# marshall.net
KiCad netlist of a schematic drawn in EAGLE
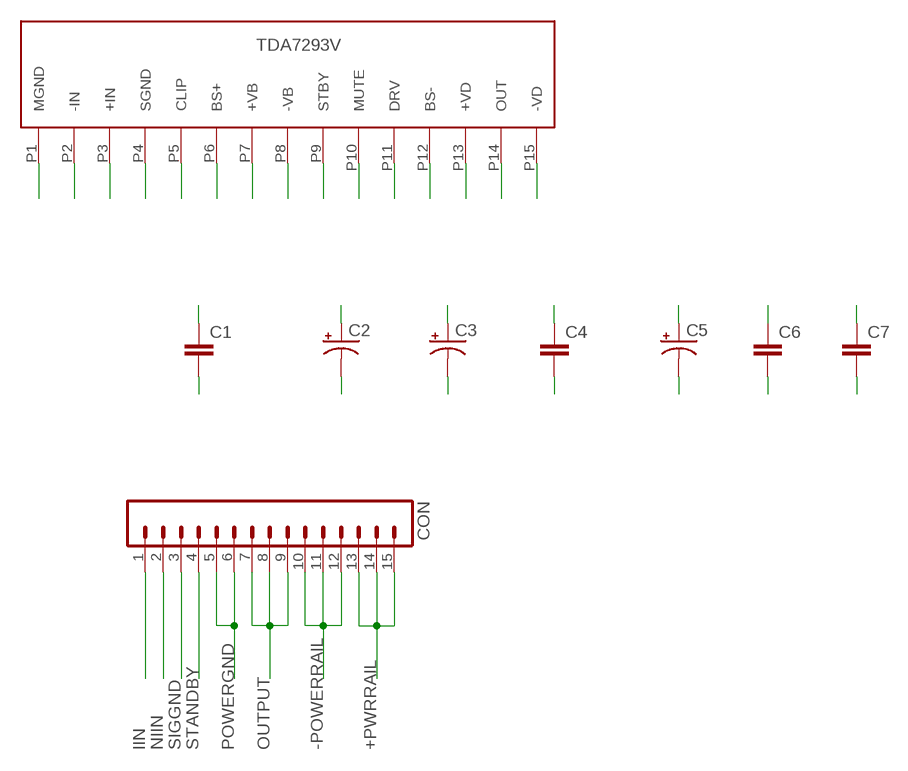
[diagram p0: schematic, sheet 1]

(export (version "E")
  (design (tool "Eeschema 10.0.6"))
  (components
    (comp (ref "C1")
      (value "CAPPTH1")
      (footprint "eagle-import:CAP-PTH-5MM")
      (libsource (lib "eagle-import") (part "CAPPTH1"))
    )
    (comp (ref "C2")
      (value "CAP_POLPTH2")
      (footprint "eagle-import:CPOL-RADIAL-10UF-25V")
      (libsource (lib "eagle-import") (part "CAP_POLPTH2"))
    )
    (comp (ref "C3")
      (value "CAP_POLPTH2")
      (footprint "eagle-import:CPOL-RADIAL-10UF-25V")
      (libsource (lib "eagle-import") (part "CAP_POLPTH2"))
    )
    (comp (ref "C4")
      (value "CAPPTH1")
      (footprint "eagle-import:CAP-PTH-5MM")
      (libsource (lib "eagle-import") (part "CAPPTH1"))
    )
    (comp (ref "C5")
      (value "CAP_POLPTH2")
      (footprint "eagle-import:CPOL-RADIAL-10UF-25V")
      (libsource (lib "eagle-import") (part "CAP_POLPTH2"))
    )
    (comp (ref "C6")
      (value "CAPPTH1")
      (footprint "eagle-import:CAP-PTH-5MM")
      (libsource (lib "eagle-import") (part "CAPPTH1"))
    )
    (comp (ref "C7")
      (value "CAPPTH1")
      (footprint "eagle-import:CAP-PTH-5MM")
      (libsource (lib "eagle-import") (part "CAPPTH1"))
    )
    (comp (ref "CON")
      (value "M15")
      (footprint "eagle-import:1X15")
      (libsource (lib "eagle-import") (part "M15"))
    )
    (comp (ref "U$1")
      (value "TDA7293V")
      (footprint "eagle-import:TDA7293V")
      (libsource (lib "eagle-import") (part "TDA7293V"))
    )
  )
  (nets
    (net (code "1") (name "/+PWRRAIL") (class "Default")
      (node (ref "C1") (pin "1") (pinfunction "1_1") (pintype "passive"))
      (node (ref "C2") (pin "1") (pinfunction "+_1") (pintype "passive"))
      (node (ref "CON") (pin "13") (pinfunction "13_13") (pintype "passive"))
      (node (ref "CON") (pin "14") (pinfunction "14_14") (pintype "passive"))
      (node (ref "CON") (pin "15") (pinfunction "15_15") (pintype "passive"))
      (node (ref "U$1") (pin "P10") (pinfunction "MUTE_P10") (pintype "bidirectional"))
      (node (ref "U$1") (pin "P13") (pinfunction "+VD_P13") (pintype "bidirectional"))
      (node (ref "U$1") (pin "P7") (pinfunction "+VB_P7") (pintype "bidirectional"))
    )
    (net (code "2") (name "/-POWERRAIL") (class "Default")
      (node (ref "C3") (pin "2") (pinfunction "-_2") (pintype "passive"))
      (node (ref "C4") (pin "1") (pinfunction "1_1") (pintype "passive"))
      (node (ref "CON") (pin "10") (pinfunction "10_10") (pintype "passive"))
      (node (ref "CON") (pin "11") (pinfunction "11_11") (pintype "passive"))
      (node (ref "CON") (pin "12") (pinfunction "12_12") (pintype "passive"))
      (node (ref "U$1") (pin "P15") (pinfunction "-VD_P15") (pintype "bidirectional"))
      (node (ref "U$1") (pin "P8") (pinfunction "-VB_P8") (pintype "bidirectional"))
    )
    (net (code "3") (name "/C5+") (class "Default")
      (node (ref "C5") (pin "1") (pinfunction "+_1") (pintype "passive"))
      (node (ref "U$1") (pin "P12") (pinfunction "BS-_P12") (pintype "bidirectional"))
    )
    (net (code "4") (name "/C5-") (class "Default")
      (node (ref "C5") (pin "2") (pinfunction "-_2") (pintype "passive"))
      (node (ref "U$1") (pin "P6") (pinfunction "BS+_P6") (pintype "bidirectional"))
    )
    (net (code "5") (name "/IIN") (class "Default")
      (node (ref "C6") (pin "2") (pinfunction "2_2") (pintype "passive"))
      (node (ref "C7") (pin "2") (pinfunction "2_2") (pintype "passive"))
      (node (ref "CON") (pin "1") (pinfunction "1_1") (pintype "passive"))
    )
    (net (code "6") (name "/NIIN") (class "Default")
      (node (ref "C6") (pin "1") (pinfunction "1_1") (pintype "passive"))
      (node (ref "CON") (pin "2") (pinfunction "2_2") (pintype "passive"))
      (node (ref "U$1") (pin "P3") (pinfunction "+IN_P3") (pintype "bidirectional"))
    )
    (net (code "7") (name "/OUTPUT") (class "Default")
      (node (ref "CON") (pin "7") (pinfunction "7_7") (pintype "passive"))
      (node (ref "CON") (pin "8") (pinfunction "8_8") (pintype "passive"))
      (node (ref "CON") (pin "9") (pinfunction "9_9") (pintype "passive"))
      (node (ref "U$1") (pin "P14") (pinfunction "OUT_P14") (pintype "bidirectional"))
    )
    (net (code "8") (name "/POWERGND") (class "Default")
      (node (ref "C1") (pin "2") (pinfunction "2_2") (pintype "passive"))
      (node (ref "C2") (pin "2") (pinfunction "-_2") (pintype "passive"))
      (node (ref "C3") (pin "1") (pinfunction "+_1") (pintype "passive"))
      (node (ref "C4") (pin "2") (pinfunction "2_2") (pintype "passive"))
      (node (ref "CON") (pin "5") (pinfunction "5_5") (pintype "passive"))
      (node (ref "CON") (pin "6") (pinfunction "6_6") (pintype "passive"))
      (node (ref "U$1") (pin "P1") (pinfunction "MGND_P1") (pintype "bidirectional"))
    )
    (net (code "9") (name "/SIGGND") (class "Default")
      (node (ref "C7") (pin "1") (pinfunction "1_1") (pintype "passive"))
      (node (ref "CON") (pin "3") (pinfunction "3_3") (pintype "passive"))
      (node (ref "U$1") (pin "P4") (pinfunction "SGND_P4") (pintype "bidirectional"))
    )
    (net (code "10") (name "/STANDBY") (class "Default")
      (node (ref "CON") (pin "4") (pinfunction "4_4") (pintype "passive"))
      (node (ref "U$1") (pin "P9") (pinfunction "STBY_P9") (pintype "bidirectional"))
    )
    (net (code "11") (name "unconnected-(U$1--IN-PadP2)") (class "Default")
      (node (ref "U$1") (pin "P2") (pinfunction "-IN_P2") (pintype "bidirectional"))
    )
    (net (code "12") (name "unconnected-(U$1-CLIP-PadP5)") (class "Default")
      (node (ref "U$1") (pin "P5") (pinfunction "CLIP_P5") (pintype "bidirectional"))
    )
    (net (code "13") (name "unconnected-(U$1-DRV-PadP11)") (class "Default")
      (node (ref "U$1") (pin "P11") (pinfunction "DRV_P11") (pintype "bidirectional"))
    )
  )
)
